# feu_85.net
KiCad netlist of a schematic drawn in EAGLE
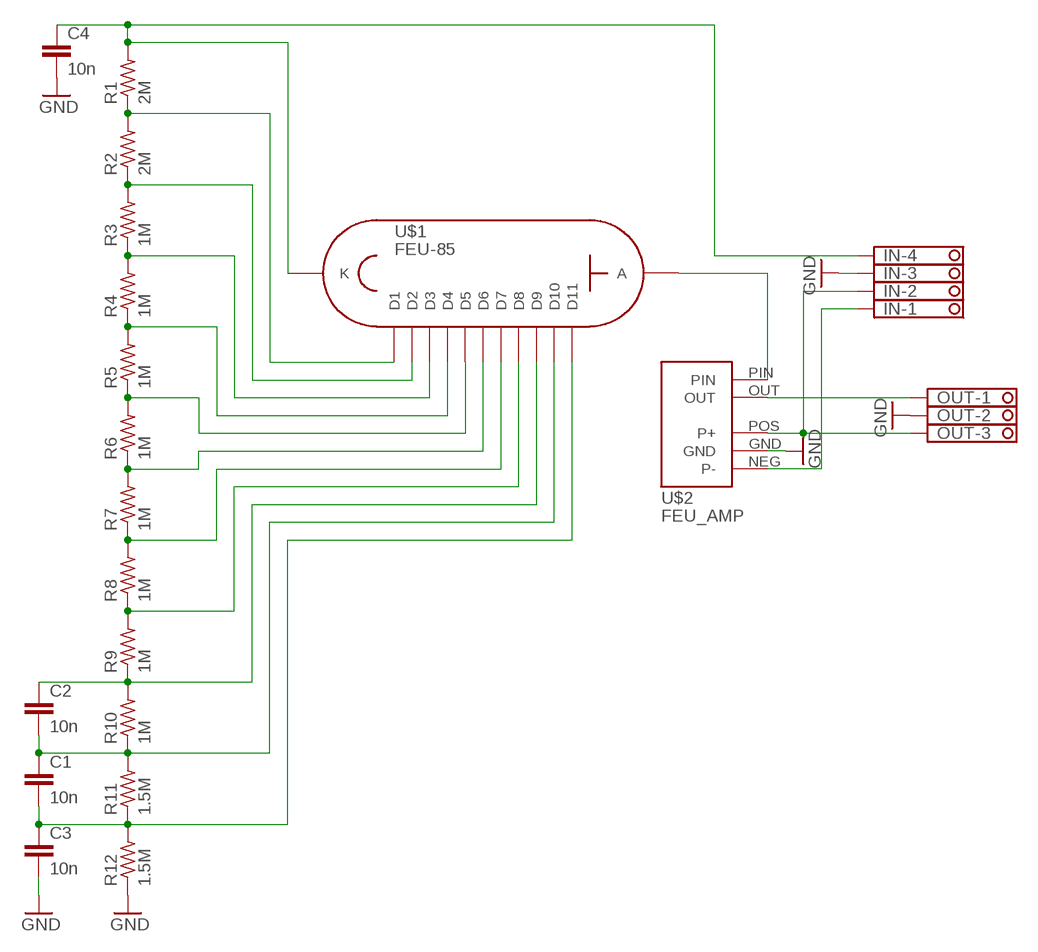
[diagram p0: schematic, sheet 1]

(export (version "E")
  (design (tool "Eeschema 10.0.6"))
  (components
    (comp (ref "C1")
      (value "10n")
      (footprint "eagle-import:C075-032X103")
      (libsource (lib "eagle-import") (part "C-EU075-032X103"))
    )
    (comp (ref "C2")
      (value "10n")
      (footprint "eagle-import:C075-032X103")
      (libsource (lib "eagle-import") (part "C-EU075-032X103"))
    )
    (comp (ref "C3")
      (value "10n")
      (footprint "eagle-import:C075-032X103")
      (libsource (lib "eagle-import") (part "C-EU075-032X103"))
    )
    (comp (ref "C4")
      (value "10n")
      (footprint "eagle-import:C225-087X268")
      (libsource (lib "eagle-import") (part "C-EU225-087X268"))
    )
    (comp (ref "IN")
      (value "1751264")
      (footprint "eagle-import:1751264")
      (libsource (lib "eagle-import") (part "1751264"))
    )
    (comp (ref "OUT")
      (value "1751251")
      (footprint "eagle-import:1751251")
      (libsource (lib "eagle-import") (part "1751251"))
    )
    (comp (ref "R1")
      (value "2M")
      (footprint "eagle-import:0207_2V")
      (libsource (lib "eagle-import") (part "R-US_0207/2V"))
    )
    (comp (ref "R2")
      (value "2M")
      (footprint "eagle-import:0207_2V")
      (libsource (lib "eagle-import") (part "R-US_0207/2V"))
    )
    (comp (ref "R3")
      (value "1M")
      (footprint "eagle-import:0207_2V")
      (libsource (lib "eagle-import") (part "R-US_0207/2V"))
    )
    (comp (ref "R4")
      (value "1M")
      (footprint "eagle-import:0207_2V")
      (libsource (lib "eagle-import") (part "R-US_0207/2V"))
    )
    (comp (ref "R5")
      (value "1M")
      (footprint "eagle-import:0207_2V")
      (libsource (lib "eagle-import") (part "R-US_0207/2V"))
    )
    (comp (ref "R6")
      (value "1M")
      (footprint "eagle-import:0207_2V")
      (libsource (lib "eagle-import") (part "R-US_0207/2V"))
    )
    (comp (ref "R7")
      (value "1M")
      (footprint "eagle-import:0207_2V")
      (libsource (lib "eagle-import") (part "R-US_0207/2V"))
    )
    (comp (ref "R8")
      (value "1M")
      (footprint "eagle-import:0207_2V")
      (libsource (lib "eagle-import") (part "R-US_0207/2V"))
    )
    (comp (ref "R9")
      (value "1M")
      (footprint "eagle-import:0207_2V")
      (libsource (lib "eagle-import") (part "R-US_0207/2V"))
    )
    (comp (ref "R10")
      (value "1M")
      (footprint "eagle-import:0207_2V")
      (libsource (lib "eagle-import") (part "R-US_0207/2V"))
    )
    (comp (ref "R11")
      (value "1.5M")
      (footprint "eagle-import:0207_2V")
      (libsource (lib "eagle-import") (part "R-US_0207/2V"))
    )
    (comp (ref "R12")
      (value "1.5M")
      (footprint "eagle-import:0207_2V")
      (libsource (lib "eagle-import") (part "R-US_0207/2V"))
    )
    (comp (ref "U$1")
      (value "FEU-85")
      (footprint "eagle-import:PANEL_14")
      (libsource (lib "eagle-import") (part "FEU-85"))
    )
    (comp (ref "U$2")
      (value "FEU_AMP")
      (footprint "eagle-import:FEU_AMP")
      (libsource (lib "eagle-import") (part "FEU_AMP"))
    )
  )
  (nets
    (net (code "1") (name "GND") (class "Default")
      (node (ref "C3") (pin "2") (pinfunction "2_2") (pintype "passive"))
      (node (ref "C4") (pin "2") (pinfunction "2_2") (pintype "passive"))
      (node (ref "IN") (pin "3") (pinfunction "K_3") (pintype "passive"))
      (node (ref "OUT") (pin "2") (pinfunction "K_2") (pintype "passive"))
      (node (ref "R12") (pin "1") (pinfunction "1_1") (pintype "passive"))
      (node (ref "U$2") (pin "GND") (pinfunction "GND_GND") (pintype "power_in"))
    )
    (net (code "2") (name "Net-(INA-K)") (class "Default")
      (node (ref "IN") (pin "1") (pinfunction "K_1") (pintype "passive"))
      (node (ref "U$2") (pin "NEG") (pinfunction "P-_NEG") (pintype "power_in"))
    )
    (net (code "3") (name "Net-(INB-K)") (class "Default")
      (node (ref "IN") (pin "2") (pinfunction "K_2") (pintype "passive"))
      (node (ref "OUT") (pin "3") (pinfunction "K_3") (pintype "passive"))
      (node (ref "U$2") (pin "POS") (pinfunction "P+_POS") (pintype "power_in"))
    )
    (net (code "4") (name "Net-(IND-K)") (class "Default")
      (node (ref "C4") (pin "1") (pinfunction "1_1") (pintype "passive"))
      (node (ref "IN") (pin "4") (pinfunction "K_4") (pintype "passive"))
      (node (ref "R1") (pin "2") (pinfunction "2_2") (pintype "passive"))
      (node (ref "U$1") (pin "P$14") (pinfunction "K_P$14") (pintype "input"))
    )
    (net (code "5") (name "Net-(OUTA-K)") (class "Default")
      (node (ref "OUT") (pin "1") (pinfunction "K_1") (pintype "passive"))
      (node (ref "U$2") (pin "OUT") (pinfunction "OUT_OUT") (pintype "output"))
    )
    (net (code "6") (name "Net-(U$1-A)") (class "Default")
      (node (ref "U$1") (pin "P$7") (pinfunction "A_P$7") (pintype "output"))
      (node (ref "U$2") (pin "PIN") (pinfunction "PIN_PIN") (pintype "input"))
    )
    (net (code "7") (name "Net-(U$1-D1)") (class "Default")
      (node (ref "R1") (pin "1") (pinfunction "1_1") (pintype "passive"))
      (node (ref "R2") (pin "2") (pinfunction "2_2") (pintype "passive"))
      (node (ref "U$1") (pin "P$13") (pinfunction "D1_P$13") (pintype "input"))
    )
    (net (code "8") (name "Net-(U$1-D2)") (class "Default")
      (node (ref "R2") (pin "1") (pinfunction "1_1") (pintype "passive"))
      (node (ref "R3") (pin "2") (pinfunction "2_2") (pintype "passive"))
      (node (ref "U$1") (pin "P$2") (pinfunction "D2_P$2") (pintype "input"))
    )
    (net (code "9") (name "Net-(U$1-D3)") (class "Default")
      (node (ref "R3") (pin "1") (pinfunction "1_1") (pintype "passive"))
      (node (ref "R4") (pin "2") (pinfunction "2_2") (pintype "passive"))
      (node (ref "U$1") (pin "P$12") (pinfunction "D3_P$12") (pintype "input"))
    )
    (net (code "10") (name "Net-(U$1-D4)") (class "Default")
      (node (ref "R4") (pin "1") (pinfunction "1_1") (pintype "passive"))
      (node (ref "R5") (pin "2") (pinfunction "2_2") (pintype "passive"))
      (node (ref "U$1") (pin "P$3") (pinfunction "D4_P$3") (pintype "input"))
    )
    (net (code "11") (name "Net-(U$1-D5)") (class "Default")
      (node (ref "R5") (pin "1") (pinfunction "1_1") (pintype "passive"))
      (node (ref "R6") (pin "2") (pinfunction "2_2") (pintype "passive"))
      (node (ref "U$1") (pin "P$11") (pinfunction "D5_P$11") (pintype "input"))
    )
    (net (code "12") (name "Net-(U$1-D6)") (class "Default")
      (node (ref "R6") (pin "1") (pinfunction "1_1") (pintype "passive"))
      (node (ref "R7") (pin "2") (pinfunction "2_2") (pintype "passive"))
      (node (ref "U$1") (pin "P$4") (pinfunction "D6_P$4") (pintype "input"))
    )
    (net (code "13") (name "Net-(U$1-D7)") (class "Default")
      (node (ref "R7") (pin "1") (pinfunction "1_1") (pintype "passive"))
      (node (ref "R8") (pin "2") (pinfunction "2_2") (pintype "passive"))
      (node (ref "U$1") (pin "P$10") (pinfunction "D7_P$10") (pintype "input"))
    )
    (net (code "14") (name "Net-(U$1-D8)") (class "Default")
      (node (ref "R8") (pin "1") (pinfunction "1_1") (pintype "passive"))
      (node (ref "R9") (pin "2") (pinfunction "2_2") (pintype "passive"))
      (node (ref "U$1") (pin "P$5") (pinfunction "D8_P$5") (pintype "input"))
    )
    (net (code "15") (name "Net-(U$1-D9)") (class "Default")
      (node (ref "C2") (pin "1") (pinfunction "1_1") (pintype "passive"))
      (node (ref "R10") (pin "2") (pinfunction "2_2") (pintype "passive"))
      (node (ref "R9") (pin "1") (pinfunction "1_1") (pintype "passive"))
      (node (ref "U$1") (pin "P$9") (pinfunction "D9_P$9") (pintype "input"))
    )
    (net (code "16") (name "Net-(U$1-D10)") (class "Default")
      (node (ref "C1") (pin "1") (pinfunction "1_1") (pintype "passive"))
      (node (ref "C2") (pin "2") (pinfunction "2_2") (pintype "passive"))
      (node (ref "R10") (pin "1") (pinfunction "1_1") (pintype "passive"))
      (node (ref "R11") (pin "2") (pinfunction "2_2") (pintype "passive"))
      (node (ref "U$1") (pin "P$6") (pinfunction "D10_P$6") (pintype "input"))
    )
    (net (code "17") (name "Net-(U$1-D11)") (class "Default")
      (node (ref "C1") (pin "2") (pinfunction "2_2") (pintype "passive"))
      (node (ref "C3") (pin "1") (pinfunction "1_1") (pintype "passive"))
      (node (ref "R11") (pin "1") (pinfunction "1_1") (pintype "passive"))
      (node (ref "R12") (pin "2") (pinfunction "2_2") (pintype "passive"))
      (node (ref "U$1") (pin "P$8") (pinfunction "D11_P$8") (pintype "input"))
    )
  )
)
